# lab2_shkabara_boost.net
KiCad netlist of a schematic drawn in Altium Designer
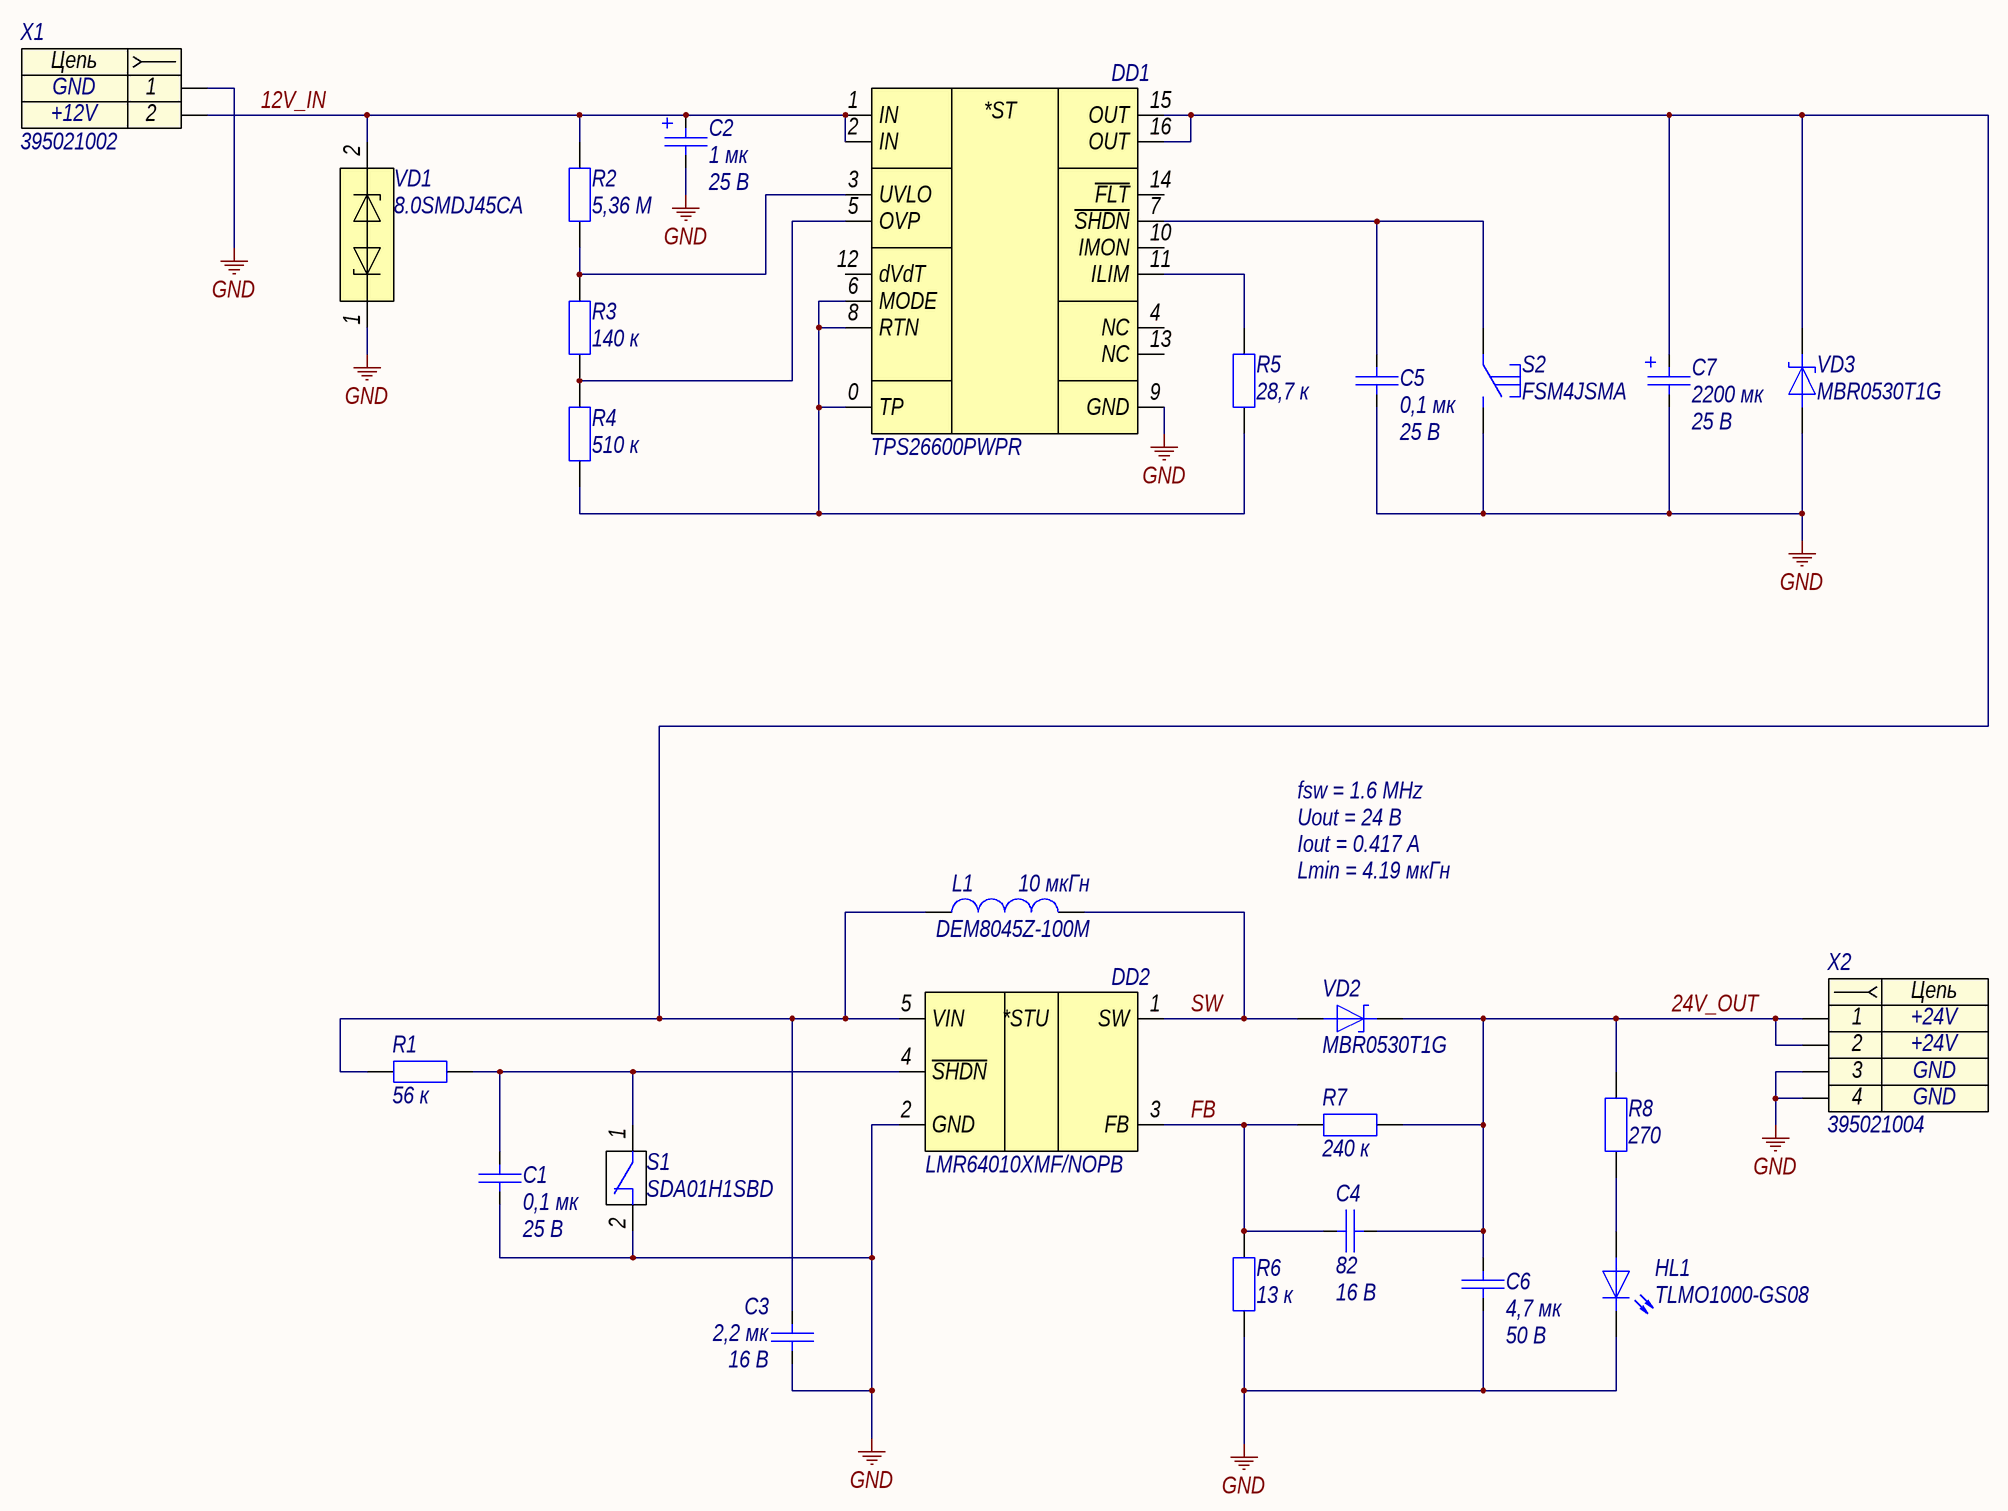
[diagram p0: lab2_shkabara_boost.SchDoc]

(export (version "E")
  (design (tool "Eeschema 10.0.6"))
  (components
    (comp (ref "C1")
      (value "0,1 мк")
      (footprint "C0402")
      (description "=Описание")
      (fields (field (name "НАПРЯЖЕНИЕ") "25 В"))
      (libsource (lib "Database_Students") (part "C-NONPOLAR"))
    )
    (comp (ref "C2")
      (value "1 мк")
      (footprint "C1206POLAR")
      (description "=Описание")
      (fields (field (name "НАПРЯЖЕНИЕ") "25 В"))
      (libsource (lib "Database_Students") (part "C-POLAR"))
    )
    (comp (ref "C3")
      (value "2,2 мк")
      (footprint "C0603")
      (description "=Описание")
      (fields (field (name "НАПРЯЖЕНИЕ") "16 В"))
      (libsource (lib "Database_Students") (part "C-NONPOLAR"))
    )
    (comp (ref "C4")
      (value "82")
      (footprint "C0603")
      (description "=Описание")
      (fields (field (name "НАПРЯЖЕНИЕ") "16 В"))
      (libsource (lib "Database_Students") (part "C-NONPOLAR"))
    )
    (comp (ref "C5")
      (value "0,1 мк")
      (footprint "C0402")
      (description "=Описание")
      (fields (field (name "НАПРЯЖЕНИЕ") "25 В"))
      (libsource (lib "Database_Students") (part "C-NONPOLAR"))
    )
    (comp (ref "C6")
      (value "4,7 мк")
      (footprint "C0805")
      (description "=Описание")
      (fields (field (name "НАПРЯЖЕНИЕ") "50 В"))
      (libsource (lib "Database_Students") (part "C-NONPOLAR"))
    )
    (comp (ref "C7")
      (value "2200 мк")
      (footprint "CAPAE-1600X1600X2100")
      (description "=Описание")
      (fields (field (name "НАПРЯЖЕНИЕ") "25 В"))
      (libsource (lib "Database_Students") (part "C-POLAR"))
    )
    (comp (ref "DD1")
      (value "TPS26600PWPR")
      (footprint "HTSSOP-16")
      (description "=Описание")
      (libsource (lib "Database_Students") (part "TPS26600PWPR"))
    )
    (comp (ref "DD2")
      (value "LMR64010XMF/NOPB")
      (footprint "SOT-23-5")
      (description "=Описание")
      (libsource (lib "Database_Students") (part "LMR64010XMF/NOPB"))
    )
    (comp (ref "HL1")
      (value "TLMO1000-GS08")
      (footprint "HL0603")
      (description "=Описание")
      (libsource (lib "Database_Students") (part "HL-COMMON"))
    )
    (comp (ref "L1")
      (value "DEM8045Z-100M")
      (footprint "DEM-2-800X800X450")
      (description "=Описание")
      (fields (field (name "ИНДУКТИВНОСТЬ") "10 мкГн"))
      (libsource (lib "Database_Students") (part "INDUCTOR-COMMON"))
    )
    (comp (ref "R1")
      (value "56 к")
      (footprint "R0603")
      (description "=Описание")
      (libsource (lib "Database_Students") (part "R-COMMON"))
    )
    (comp (ref "R2")
      (value "5,36 M")
      (footprint "R0603")
      (description "=Описание")
      (libsource (lib "Database_Students") (part "R-COMMON"))
    )
    (comp (ref "R3")
      (value "140 к")
      (footprint "R0603")
      (description "=Описание")
      (libsource (lib "Database_Students") (part "R-COMMON"))
    )
    (comp (ref "R4")
      (value "510 к")
      (footprint "R0603")
      (description "=Описание")
      (libsource (lib "Database_Students") (part "R-COMMON"))
    )
    (comp (ref "R5")
      (value "28,7 к")
      (footprint "R0603")
      (description "=Описание")
      (libsource (lib "Database_Students") (part "R-COMMON"))
    )
    (comp (ref "R6")
      (value "13 к")
      (footprint "R0603")
      (description "=Описание")
      (libsource (lib "Database_Students") (part "R-COMMON"))
    )
    (comp (ref "R7")
      (value "240 к")
      (footprint "R0603")
      (description "=Описание")
      (libsource (lib "Database_Students") (part "R-COMMON"))
    )
    (comp (ref "R8")
      (value "270")
      (footprint "R0603")
      (description "=Описание")
      (libsource (lib "Database_Students") (part "R-COMMON"))
    )
    (comp (ref "S1")
      (value "SDA01H1SBD")
      (footprint "DIP-SWITCH-01-452X930X545")
      (description "=Описание")
      (libsource (lib "Database_Students") (part "SWITCH-01"))
    )
    (comp (ref "S2")
      (value "FSM4JSMA")
      (footprint "FSM4JSMA")
      (description "=Описание")
      (libsource (lib "Database_Students") (part "BUTTON"))
    )
    (comp (ref "VD1")
      (value "8.0SMDJ45CA")
      (footprint "DO-214AB")
      (description "=Описание")
      (libsource (lib "Database_Students") (part "ZENER-BI-DIRECTIONAL"))
    )
    (comp (ref "VD2")
      (value "MBR0530T1G")
      (footprint "SOD-123")
      (description "=Описание")
      (libsource (lib "Database_Students") (part "DIODE-SCHOTTKY"))
    )
    (comp (ref "VD3")
      (value "MBR0530T1G")
      (footprint "SOD-123")
      (description "=Описание")
      (libsource (lib "Database_Students") (part "DIODE-SCHOTTKY"))
    )
    (comp (ref "X1")
      (value "395021002")
      (footprint "395021002")
      (description "=Описание")
      (libsource (lib "Database_Students") (part "HEADER-2-SCT"))
    )
    (comp (ref "X2")
      (value "395021004")
      (footprint "395021004")
      (description "=Описание")
      (libsource (lib "Database_Students") (part "HEADER-4-SCT"))
    )
  )
  (nets
    (net (code "1") (name "/12V_IN") (class "Default")
      (node (ref "C2") (pin "1") (pinfunction "1_1") (pintype "passive"))
      (node (ref "DD1") (pin "1") (pinfunction "IN_1") (pintype "passive"))
      (node (ref "DD1") (pin "2") (pinfunction "IN_2") (pintype "passive"))
      (node (ref "R2") (pin "2") (pinfunction "2_2") (pintype "passive"))
      (node (ref "VD1") (pin "2") (pinfunction "2_2") (pintype "passive"))
      (node (ref "X1") (pin "2") (pinfunction "2_2") (pintype "passive"))
    )
    (net (code "2") (name "/24V_OUT") (class "Default")
      (node (ref "C4") (pin "1") (pinfunction "1_1") (pintype "passive"))
      (node (ref "C6") (pin "1") (pinfunction "1_1") (pintype "passive"))
      (node (ref "R7") (pin "2") (pinfunction "2_2") (pintype "passive"))
      (node (ref "R8") (pin "2") (pinfunction "2_2") (pintype "passive"))
      (node (ref "VD2") (pin "1") (pinfunction "1_1") (pintype "passive"))
      (node (ref "X2") (pin "1") (pinfunction "1_1") (pintype "passive"))
      (node (ref "X2") (pin "2") (pinfunction "2_2") (pintype "passive"))
    )
    (net (code "3") (name "/FB") (class "Default")
      (node (ref "C4") (pin "2") (pinfunction "2_2") (pintype "passive"))
      (node (ref "DD2") (pin "3") (pinfunction "FB_3") (pintype "passive"))
      (node (ref "R6") (pin "2") (pinfunction "2_2") (pintype "passive"))
      (node (ref "R7") (pin "1") (pinfunction "1_1") (pintype "passive"))
    )
    (net (code "4") (name "/SW") (class "Default")
      (node (ref "DD2") (pin "1") (pinfunction "SW_1") (pintype "passive"))
      (node (ref "L1") (pin "2") (pinfunction "2_2") (pintype "passive"))
      (node (ref "VD2") (pin "2") (pinfunction "2_2") (pintype "passive"))
    )
    (net (code "5") (name "GND") (class "Default")
      (node (ref "C1") (pin "2") (pinfunction "2_2") (pintype "passive"))
      (node (ref "C2") (pin "2") (pinfunction "2_2") (pintype "passive"))
      (node (ref "C3") (pin "2") (pinfunction "2_2") (pintype "passive"))
      (node (ref "C5") (pin "2") (pinfunction "2_2") (pintype "passive"))
      (node (ref "C6") (pin "2") (pinfunction "2_2") (pintype "passive"))
      (node (ref "C7") (pin "2") (pinfunction "2_2") (pintype "passive"))
      (node (ref "DD1") (pin "9") (pinfunction "GND_9") (pintype "passive"))
      (node (ref "DD2") (pin "2") (pinfunction "GND_2") (pintype "passive"))
      (node (ref "HL1") (pin "1") (pinfunction "1_1") (pintype "passive"))
      (node (ref "R6") (pin "1") (pinfunction "1_1") (pintype "passive"))
      (node (ref "S1") (pin "2") (pinfunction "2_2") (pintype "passive"))
      (node (ref "S2") (pin "2") (pinfunction "2_2") (pintype "passive"))
      (node (ref "VD1") (pin "1") (pinfunction "1_1") (pintype "passive"))
      (node (ref "VD3") (pin "2") (pinfunction "2_2") (pintype "passive"))
      (node (ref "X1") (pin "1") (pinfunction "1_1") (pintype "passive"))
      (node (ref "X2") (pin "3") (pinfunction "3_3") (pintype "passive"))
      (node (ref "X2") (pin "4") (pinfunction "4_4") (pintype "passive"))
    )
    (net (code "6") (name "Net-(DD1-ILIM)") (class "Default")
      (node (ref "DD1") (pin "11") (pinfunction "ILIM_11") (pintype "passive"))
      (node (ref "R5") (pin "2") (pinfunction "2_2") (pintype "passive"))
    )
    (net (code "7") (name "Net-(DD1-MODE)") (class "Default")
      (node (ref "DD1") (pin "0") (pinfunction "TP_0") (pintype "passive"))
      (node (ref "DD1") (pin "6") (pinfunction "MODE_6") (pintype "passive"))
      (node (ref "DD1") (pin "8") (pinfunction "RTN_8") (pintype "passive"))
      (node (ref "R4") (pin "1") (pinfunction "1_1") (pintype "passive"))
      (node (ref "R5") (pin "1") (pinfunction "1_1") (pintype "passive"))
    )
    (net (code "8") (name "Net-(DD1-OVP)") (class "Default")
      (node (ref "DD1") (pin "5") (pinfunction "OVP_5") (pintype "passive"))
      (node (ref "R3") (pin "1") (pinfunction "1_1") (pintype "passive"))
      (node (ref "R4") (pin "2") (pinfunction "2_2") (pintype "passive"))
    )
    (net (code "9") (name "Net-(DD1-UVLO)") (class "Default")
      (node (ref "DD1") (pin "3") (pinfunction "UVLO_3") (pintype "passive"))
      (node (ref "R2") (pin "1") (pinfunction "1_1") (pintype "passive"))
      (node (ref "R3") (pin "2") (pinfunction "2_2") (pintype "passive"))
    )
    (net (code "10") (name "Net-(DD1-~{SHDN})") (class "Default")
      (node (ref "C5") (pin "1") (pinfunction "1_1") (pintype "passive"))
      (node (ref "DD1") (pin "7") (pinfunction "~{SHDN}_7") (pintype "passive"))
      (node (ref "S2") (pin "1") (pinfunction "1_1") (pintype "passive"))
    )
    (net (code "11") (name "Net-(DD2-VIN)") (class "Default")
      (node (ref "C3") (pin "1") (pinfunction "1_1") (pintype "passive"))
      (node (ref "C7") (pin "1") (pinfunction "1_1") (pintype "passive"))
      (node (ref "DD1") (pin "15") (pinfunction "OUT_15") (pintype "passive"))
      (node (ref "DD1") (pin "16") (pinfunction "OUT_16") (pintype "passive"))
      (node (ref "DD2") (pin "5") (pinfunction "VIN_5") (pintype "passive"))
      (node (ref "L1") (pin "1") (pinfunction "1_1") (pintype "passive"))
      (node (ref "R1") (pin "2") (pinfunction "2_2") (pintype "passive"))
      (node (ref "VD3") (pin "1") (pinfunction "1_1") (pintype "passive"))
    )
    (net (code "12") (name "Net-(DD2-~{SHDN})") (class "Default")
      (node (ref "C1") (pin "1") (pinfunction "1_1") (pintype "passive"))
      (node (ref "DD2") (pin "4") (pinfunction "~{SHDN}_4") (pintype "passive"))
      (node (ref "R1") (pin "1") (pinfunction "1_1") (pintype "passive"))
      (node (ref "S1") (pin "1") (pinfunction "1_1") (pintype "passive"))
    )
    (net (code "13") (name "Net-(HL1-Pad2)") (class "Default")
      (node (ref "HL1") (pin "2") (pinfunction "2_2") (pintype "passive"))
      (node (ref "R8") (pin "1") (pinfunction "1_1") (pintype "passive"))
    )
    (net (code "14") (name "unconnected-(DD1-IMON-Pad10)") (class "Default")
      (node (ref "DD1") (pin "10") (pinfunction "IMON_10") (pintype "passive"))
    )
    (net (code "15") (name "unconnected-(DD1-NC-Pad4)") (class "Default")
      (node (ref "DD1") (pin "4") (pinfunction "NC_4") (pintype "passive"))
    )
    (net (code "16") (name "unconnected-(DD1-NC-Pad13)") (class "Default")
      (node (ref "DD1") (pin "13") (pinfunction "NC_13") (pintype "passive"))
    )
    (net (code "17") (name "unconnected-(DD1-dVdT-Pad12)") (class "Default")
      (node (ref "DD1") (pin "12") (pinfunction "dVdT_12") (pintype "passive"))
    )
    (net (code "18") (name "unconnected-(DD1-~{FLT}-Pad14)") (class "Default")
      (node (ref "DD1") (pin "14") (pinfunction "~{FLT}_14") (pintype "passive"))
    )
  )
)
